# hall_switches.net
KiCad netlist of a schematic drawn in Altium Designer
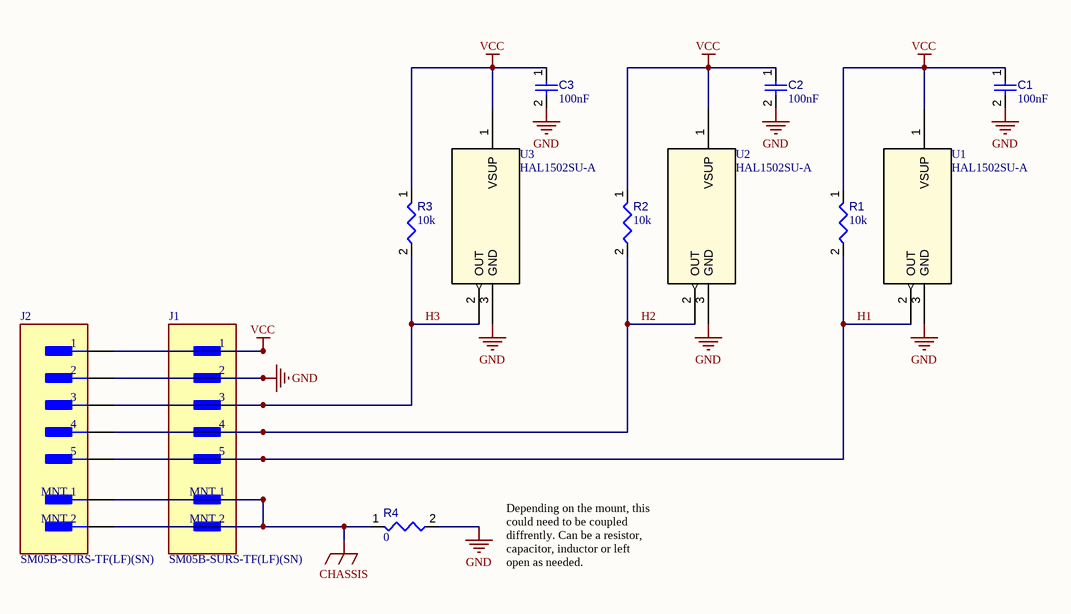
[diagram p0: hall_switches.SchDoc]

(export (version "E")
  (design (tool "Eeschema 10.0.6"))
  (components
    (comp (ref "C1")
      (value "100nF")
      (footprint "CAPC2013X95X50ML10T25")
      (description "Chip Capacitor, 100 nF, +/- 10%, 50 V, 0805 (2012 Metric)")
      (fields (field (name "TOLERANCE") "10%") (field (name "Comment") "Capacitor 100 nF +/-10% 50 V 0805"))
      (libsource (lib "Trek Bicycle Corporation") (part "CAP-NP-2"))
    )
    (comp (ref "C2")
      (value "100nF")
      (footprint "CAPC2013X95X50ML10T25")
      (description "Chip Capacitor, 100 nF, +/- 10%, 50 V, 0805 (2012 Metric)")
      (fields (field (name "TOLERANCE") "10%") (field (name "Comment") "Capacitor 100 nF +/-10% 50 V 0805"))
      (libsource (lib "Trek Bicycle Corporation") (part "CAP-NP-2"))
    )
    (comp (ref "C3")
      (value "100nF")
      (footprint "CAPC2013X95X50ML10T25")
      (description "Chip Capacitor, 100 nF, +/- 10%, 50 V, 0805 (2012 Metric)")
      (fields (field (name "TOLERANCE") "10%") (field (name "Comment") "Capacitor 100 nF +/-10% 50 V 0805"))
      (libsource (lib "Trek Bicycle Corporation") (part "CAP-NP-2"))
    )
    (comp (ref "J1")
      (value "SM05B-SURS-TF(LF)(SN)")
      (footprint "FP-SM05B-SURS-TF_LF_SN-MFG")
      (description "CONN HEADER SMD R/A 5POS 0.8MM")
      (libsource (lib "Altium Content Vault") (part "92180a1817894eac3ca0446ac55cad9"))
    )
    (comp (ref "J2")
      (value "SM05B-SURS-TF(LF)(SN)")
      (footprint "FP-SM05B-SURS-TF_LF_SN-MFG")
      (description "CONN HEADER SMD R/A 5POS 0.8MM")
      (libsource (lib "Altium Content Vault") (part "92180a1817894eac3ca0446ac55cad9"))
    )
    (comp (ref "R1")
      (value "10k")
      (footprint "RESC2013X50X35ML15T15")
      (description "Chip Resistor, 10 KOhm, +/- 1%, 125 mW, -55 to 155 degC, 0805 (2012 Metric)")
      (fields (field (name "TOLERANCE") "1%") (field (name "POWER") "125mW"))
      (libsource (lib "Greg Berkeley") (part "RES-2"))
    )
    (comp (ref "R2")
      (value "10k")
      (footprint "RESC2013X50X35ML15T15")
      (description "Chip Resistor, 10 KOhm, +/- 1%, 125 mW, -55 to 155 degC, 0805 (2012 Metric)")
      (fields (field (name "TOLERANCE") "1%") (field (name "POWER") "125mW"))
      (libsource (lib "Greg Berkeley") (part "RES-2"))
    )
    (comp (ref "R3")
      (value "10k")
      (footprint "RESC2013X50X35ML15T15")
      (description "Chip Resistor, 10 KOhm, +/- 1%, 125 mW, -55 to 155 degC, 0805 (2012 Metric)")
      (fields (field (name "TOLERANCE") "1%") (field (name "POWER") "125mW"))
      (libsource (lib "altium-import") (part "root_3_mirrored_RES-2_"))
    )
    (comp (ref "R4")
      (value "0")
      (footprint "RESC0805(2012)_L")
      (description "0.125W 5% 0805 (2012 Metric)  SMD")
      (fields (field (name "TOLERANCE") "5%") (field (name "POWER") "125mW"))
      (libsource (lib "Trek Bicycle Corporation") (part "CMP-009-00102-1"))
    )
    (comp (ref "U1")
      (value "HAL1502SU-A")
      (footprint "SOT-23_TO-236_TDK")
      (description "No Description Available")
      (fields (field (name "COPYRIGHT") "Copyright (C) 2024 Ultra Librarian. All rights reserved."))
      (libsource (lib "HAL1502SU-A") (part "HAL1502SU-A"))
    )
    (comp (ref "U2")
      (value "HAL1502SU-A")
      (footprint "SOT-23_TO-236_TDK")
      (description "No Description Available")
      (fields (field (name "COPYRIGHT") "Copyright (C) 2024 Ultra Librarian. All rights reserved."))
      (libsource (lib "HAL1502SU-A") (part "HAL1502SU-A"))
    )
    (comp (ref "U3")
      (value "HAL1502SU-A")
      (footprint "SOT-23_TO-236_TDK")
      (description "No Description Available")
      (fields (field (name "COPYRIGHT") "Copyright (C) 2024 Ultra Librarian. All rights reserved."))
      (libsource (lib "HAL1502SU-A") (part "HAL1502SU-A"))
    )
  )
  (nets
    (net (code "1") (name "/H1") (class "Default")
      (node (ref "J1") (pin "5") (pinfunction "5_5") (pintype "passive"))
      (node (ref "J2") (pin "5") (pinfunction "5_5") (pintype "passive"))
      (node (ref "R1") (pin "2") (pinfunction "2_2") (pintype "passive"))
      (node (ref "U1") (pin "2") (pinfunction "OUT_2") (pintype "output"))
    )
    (net (code "2") (name "/H2") (class "Default")
      (node (ref "J1") (pin "4") (pinfunction "4_4") (pintype "passive"))
      (node (ref "J2") (pin "4") (pinfunction "4_4") (pintype "passive"))
      (node (ref "R2") (pin "2") (pinfunction "2_2") (pintype "passive"))
      (node (ref "U2") (pin "2") (pinfunction "OUT_2") (pintype "output"))
    )
    (net (code "3") (name "/H3") (class "Default")
      (node (ref "J1") (pin "3") (pinfunction "3_3") (pintype "passive"))
      (node (ref "J2") (pin "3") (pinfunction "3_3") (pintype "passive"))
      (node (ref "R3") (pin "2") (pinfunction "2_2") (pintype "passive"))
      (node (ref "U3") (pin "2") (pinfunction "OUT_2") (pintype "output"))
    )
    (net (code "4") (name "CHASSIS") (class "Default")
      (node (ref "J1") (pin "6") (pinfunction "MNT_1_6") (pintype "passive"))
      (node (ref "J1") (pin "7") (pinfunction "MNT_2_7") (pintype "passive"))
      (node (ref "J2") (pin "6") (pinfunction "MNT_1_6") (pintype "passive"))
      (node (ref "J2") (pin "7") (pinfunction "MNT_2_7") (pintype "passive"))
      (node (ref "R4") (pin "1") (pinfunction "1_1") (pintype "passive"))
    )
    (net (code "5") (name "GND") (class "Default")
      (node (ref "C1") (pin "2") (pinfunction "2_2") (pintype "passive"))
      (node (ref "C2") (pin "2") (pinfunction "2_2") (pintype "passive"))
      (node (ref "C3") (pin "2") (pinfunction "2_2") (pintype "passive"))
      (node (ref "J1") (pin "2") (pinfunction "2_2") (pintype "passive"))
      (node (ref "J2") (pin "2") (pinfunction "2_2") (pintype "passive"))
      (node (ref "R4") (pin "2") (pinfunction "2_2") (pintype "passive"))
      (node (ref "U1") (pin "3") (pinfunction "GND_3") (pintype "power_in"))
      (node (ref "U2") (pin "3") (pinfunction "GND_3") (pintype "power_in"))
      (node (ref "U3") (pin "3") (pinfunction "GND_3") (pintype "power_in"))
    )
    (net (code "6") (name "VCC") (class "Default")
      (node (ref "C1") (pin "1") (pinfunction "1_1") (pintype "passive"))
      (node (ref "C2") (pin "1") (pinfunction "1_1") (pintype "passive"))
      (node (ref "C3") (pin "1") (pinfunction "1_1") (pintype "passive"))
      (node (ref "J1") (pin "1") (pinfunction "1_1") (pintype "passive"))
      (node (ref "J2") (pin "1") (pinfunction "1_1") (pintype "passive"))
      (node (ref "R1") (pin "1") (pinfunction "1_1") (pintype "passive"))
      (node (ref "R2") (pin "1") (pinfunction "1_1") (pintype "passive"))
      (node (ref "R3") (pin "1") (pinfunction "1_1") (pintype "passive"))
      (node (ref "U1") (pin "1") (pinfunction "VSUP_1") (pintype "power_in"))
      (node (ref "U2") (pin "1") (pinfunction "VSUP_1") (pintype "power_in"))
      (node (ref "U3") (pin "1") (pinfunction "VSUP_1") (pintype "power_in"))
    )
  )
)
